# connector_16x4.net
KiCad netlist of a schematic drawn in EAGLE
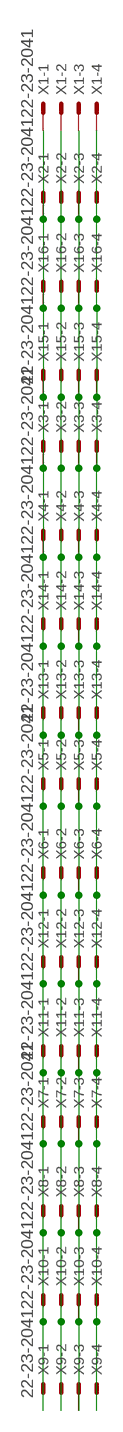
[diagram p0: schematic, sheet 1]

(export (version "E")
  (design (tool "Eeschema 10.0.6"))
  (components
    (comp (ref "X1")
      (value "22-23-2041")
      (footprint "eagle-import:22-23-2041")
      (fields (field (name "MF") "MOLEX"))
      (libsource (lib "eagle-import") (part "22-23-2041"))
    )
    (comp (ref "X2")
      (value "22-23-2041")
      (footprint "eagle-import:22-23-2041")
      (fields (field (name "MF") "MOLEX"))
      (libsource (lib "eagle-import") (part "22-23-2041"))
    )
    (comp (ref "X3")
      (value "22-23-2041")
      (footprint "eagle-import:22-23-2041")
      (fields (field (name "MF") "MOLEX"))
      (libsource (lib "eagle-import") (part "22-23-2041"))
    )
    (comp (ref "X4")
      (value "22-23-2041")
      (footprint "eagle-import:22-23-2041")
      (fields (field (name "MF") "MOLEX"))
      (libsource (lib "eagle-import") (part "22-23-2041"))
    )
    (comp (ref "X5")
      (value "22-23-2041")
      (footprint "eagle-import:22-23-2041")
      (fields (field (name "MF") "MOLEX"))
      (libsource (lib "eagle-import") (part "22-23-2041"))
    )
    (comp (ref "X6")
      (value "22-23-2041")
      (footprint "eagle-import:22-23-2041")
      (fields (field (name "MF") "MOLEX"))
      (libsource (lib "eagle-import") (part "22-23-2041"))
    )
    (comp (ref "X7")
      (value "22-23-2041")
      (footprint "eagle-import:22-23-2041")
      (fields (field (name "MF") "MOLEX"))
      (libsource (lib "eagle-import") (part "22-23-2041"))
    )
    (comp (ref "X8")
      (value "22-23-2041")
      (footprint "eagle-import:22-23-2041")
      (fields (field (name "MF") "MOLEX"))
      (libsource (lib "eagle-import") (part "22-23-2041"))
    )
    (comp (ref "X9")
      (value "22-23-2041")
      (footprint "eagle-import:22-23-2041")
      (fields (field (name "MF") "MOLEX"))
      (libsource (lib "eagle-import") (part "22-23-2041"))
    )
    (comp (ref "X10")
      (value "22-23-2041")
      (footprint "eagle-import:22-23-2041")
      (fields (field (name "MF") "MOLEX"))
      (libsource (lib "eagle-import") (part "22-23-2041"))
    )
    (comp (ref "X11")
      (value "22-23-2041")
      (footprint "eagle-import:22-23-2041")
      (fields (field (name "MF") "MOLEX"))
      (libsource (lib "eagle-import") (part "22-23-2041"))
    )
    (comp (ref "X12")
      (value "22-23-2041")
      (footprint "eagle-import:22-23-2041")
      (fields (field (name "MF") "MOLEX"))
      (libsource (lib "eagle-import") (part "22-23-2041"))
    )
    (comp (ref "X13")
      (value "22-23-2041")
      (footprint "eagle-import:22-23-2041")
      (fields (field (name "MF") "MOLEX"))
      (libsource (lib "eagle-import") (part "22-23-2041"))
    )
    (comp (ref "X14")
      (value "22-23-2041")
      (footprint "eagle-import:22-23-2041")
      (fields (field (name "MF") "MOLEX"))
      (libsource (lib "eagle-import") (part "22-23-2041"))
    )
    (comp (ref "X15")
      (value "22-23-2041")
      (footprint "eagle-import:22-23-2041")
      (fields (field (name "MF") "MOLEX"))
      (libsource (lib "eagle-import") (part "22-23-2041"))
    )
    (comp (ref "X16")
      (value "22-23-2041")
      (footprint "eagle-import:22-23-2041")
      (fields (field (name "MF") "MOLEX"))
      (libsource (lib "eagle-import") (part "22-23-2041"))
    )
  )
  (nets
    (net (code "1") (name "Net-(X10A-S)") (class "Default")
      (node (ref "X1") (pin "1") (pinfunction "S_1") (pintype "passive"))
      (node (ref "X10") (pin "1") (pinfunction "S_1") (pintype "passive"))
      (node (ref "X11") (pin "1") (pinfunction "S_1") (pintype "passive"))
      (node (ref "X12") (pin "1") (pinfunction "S_1") (pintype "passive"))
      (node (ref "X13") (pin "1") (pinfunction "S_1") (pintype "passive"))
      (node (ref "X14") (pin "1") (pinfunction "S_1") (pintype "passive"))
      (node (ref "X15") (pin "1") (pinfunction "S_1") (pintype "passive"))
      (node (ref "X16") (pin "1") (pinfunction "S_1") (pintype "passive"))
      (node (ref "X2") (pin "1") (pinfunction "S_1") (pintype "passive"))
      (node (ref "X3") (pin "1") (pinfunction "S_1") (pintype "passive"))
      (node (ref "X4") (pin "1") (pinfunction "S_1") (pintype "passive"))
      (node (ref "X5") (pin "1") (pinfunction "S_1") (pintype "passive"))
      (node (ref "X6") (pin "1") (pinfunction "S_1") (pintype "passive"))
      (node (ref "X7") (pin "1") (pinfunction "S_1") (pintype "passive"))
      (node (ref "X8") (pin "1") (pinfunction "S_1") (pintype "passive"))
      (node (ref "X9") (pin "1") (pinfunction "S_1") (pintype "passive"))
    )
    (net (code "2") (name "Net-(X10B-S)") (class "Default")
      (node (ref "X1") (pin "2") (pinfunction "S_2") (pintype "passive"))
      (node (ref "X10") (pin "2") (pinfunction "S_2") (pintype "passive"))
      (node (ref "X11") (pin "2") (pinfunction "S_2") (pintype "passive"))
      (node (ref "X12") (pin "2") (pinfunction "S_2") (pintype "passive"))
      (node (ref "X13") (pin "2") (pinfunction "S_2") (pintype "passive"))
      (node (ref "X14") (pin "2") (pinfunction "S_2") (pintype "passive"))
      (node (ref "X15") (pin "2") (pinfunction "S_2") (pintype "passive"))
      (node (ref "X16") (pin "2") (pinfunction "S_2") (pintype "passive"))
      (node (ref "X2") (pin "2") (pinfunction "S_2") (pintype "passive"))
      (node (ref "X3") (pin "2") (pinfunction "S_2") (pintype "passive"))
      (node (ref "X4") (pin "2") (pinfunction "S_2") (pintype "passive"))
      (node (ref "X5") (pin "2") (pinfunction "S_2") (pintype "passive"))
      (node (ref "X6") (pin "2") (pinfunction "S_2") (pintype "passive"))
      (node (ref "X7") (pin "2") (pinfunction "S_2") (pintype "passive"))
      (node (ref "X8") (pin "2") (pinfunction "S_2") (pintype "passive"))
      (node (ref "X9") (pin "2") (pinfunction "S_2") (pintype "passive"))
    )
    (net (code "3") (name "Net-(X10C-S)") (class "Default")
      (node (ref "X1") (pin "3") (pinfunction "S_3") (pintype "passive"))
      (node (ref "X10") (pin "3") (pinfunction "S_3") (pintype "passive"))
      (node (ref "X11") (pin "3") (pinfunction "S_3") (pintype "passive"))
      (node (ref "X12") (pin "3") (pinfunction "S_3") (pintype "passive"))
      (node (ref "X13") (pin "3") (pinfunction "S_3") (pintype "passive"))
      (node (ref "X14") (pin "3") (pinfunction "S_3") (pintype "passive"))
      (node (ref "X15") (pin "3") (pinfunction "S_3") (pintype "passive"))
      (node (ref "X16") (pin "3") (pinfunction "S_3") (pintype "passive"))
      (node (ref "X2") (pin "3") (pinfunction "S_3") (pintype "passive"))
      (node (ref "X3") (pin "3") (pinfunction "S_3") (pintype "passive"))
      (node (ref "X4") (pin "3") (pinfunction "S_3") (pintype "passive"))
      (node (ref "X5") (pin "3") (pinfunction "S_3") (pintype "passive"))
      (node (ref "X6") (pin "3") (pinfunction "S_3") (pintype "passive"))
      (node (ref "X7") (pin "3") (pinfunction "S_3") (pintype "passive"))
      (node (ref "X8") (pin "3") (pinfunction "S_3") (pintype "passive"))
      (node (ref "X9") (pin "3") (pinfunction "S_3") (pintype "passive"))
    )
    (net (code "4") (name "Net-(X10D-S)") (class "Default")
      (node (ref "X1") (pin "4") (pinfunction "S_4") (pintype "passive"))
      (node (ref "X10") (pin "4") (pinfunction "S_4") (pintype "passive"))
      (node (ref "X11") (pin "4") (pinfunction "S_4") (pintype "passive"))
      (node (ref "X12") (pin "4") (pinfunction "S_4") (pintype "passive"))
      (node (ref "X13") (pin "4") (pinfunction "S_4") (pintype "passive"))
      (node (ref "X14") (pin "4") (pinfunction "S_4") (pintype "passive"))
      (node (ref "X15") (pin "4") (pinfunction "S_4") (pintype "passive"))
      (node (ref "X16") (pin "4") (pinfunction "S_4") (pintype "passive"))
      (node (ref "X2") (pin "4") (pinfunction "S_4") (pintype "passive"))
      (node (ref "X3") (pin "4") (pinfunction "S_4") (pintype "passive"))
      (node (ref "X4") (pin "4") (pinfunction "S_4") (pintype "passive"))
      (node (ref "X5") (pin "4") (pinfunction "S_4") (pintype "passive"))
      (node (ref "X6") (pin "4") (pinfunction "S_4") (pintype "passive"))
      (node (ref "X7") (pin "4") (pinfunction "S_4") (pintype "passive"))
      (node (ref "X8") (pin "4") (pinfunction "S_4") (pintype "passive"))
      (node (ref "X9") (pin "4") (pinfunction "S_4") (pintype "passive"))
    )
  )
)
